# resistor-rc-filters.net
KiCad netlist of a schematic drawn in EAGLE
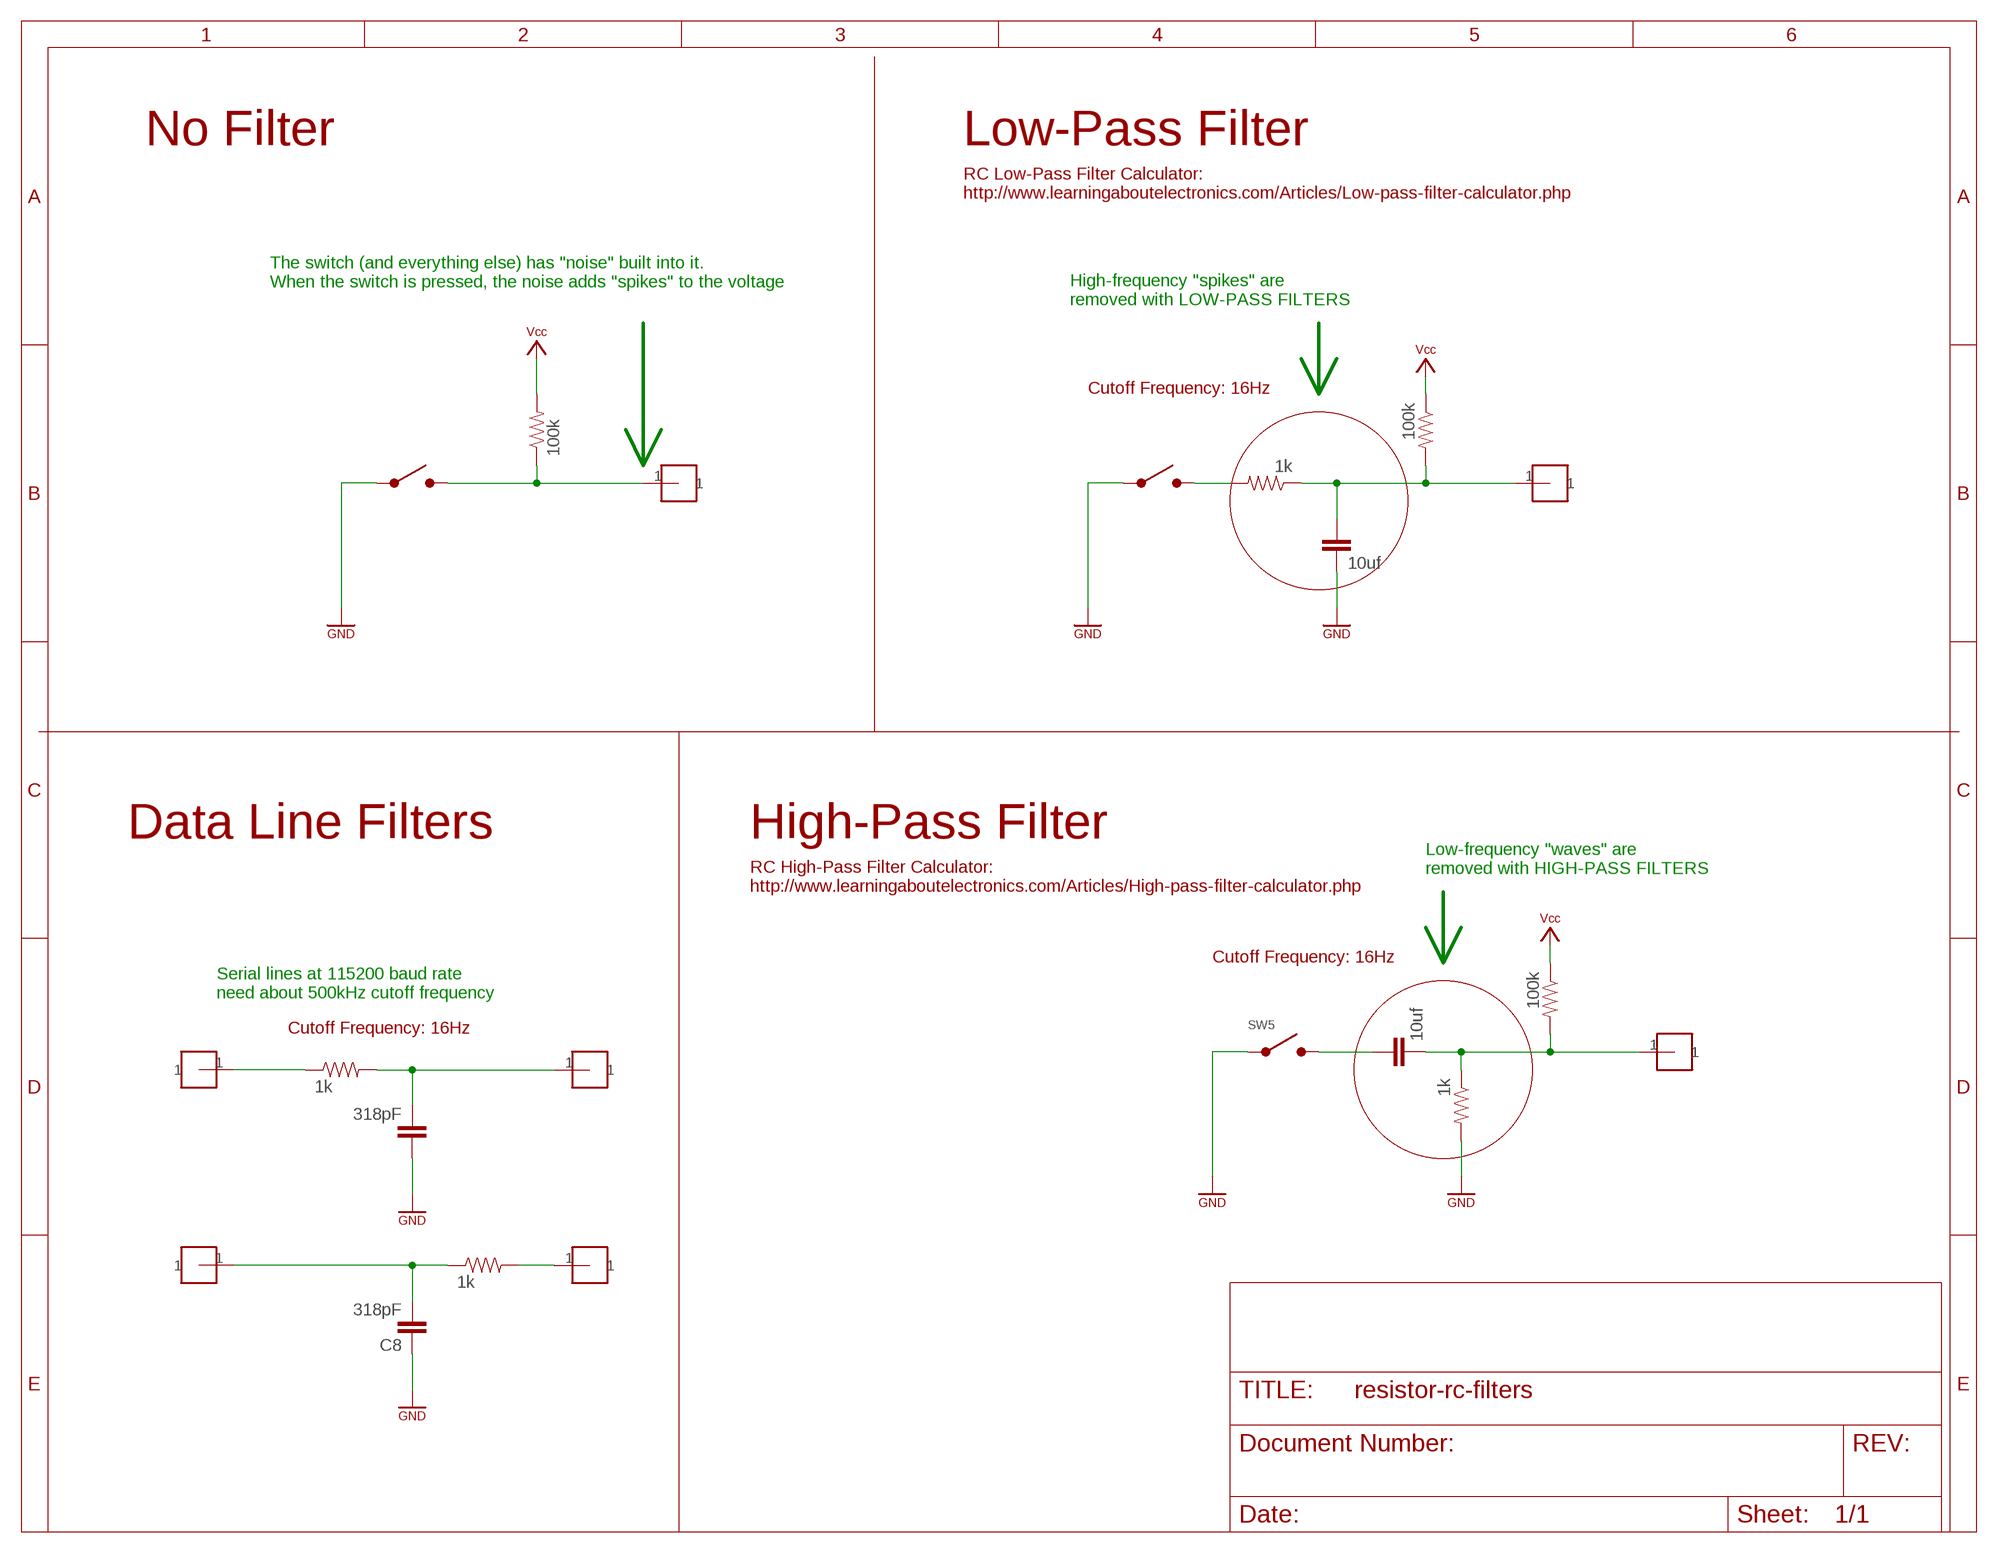
[diagram p0: schematic, sheet 1]

(export (version "E")
  (design (tool "Eeschema 10.0.6"))
  (components
    (comp (ref "C5")
      (value "10uf")
      (footprint "eagle-import:0805")
      (libsource (lib "eagle-import") (part "COMPONENT_CAP-0805"))
    )
    (comp (ref "C6")
      (value "10uf")
      (footprint "eagle-import:0805")
      (libsource (lib "eagle-import") (part "COMPONENT_CAP-0805"))
    )
    (comp (ref "C7")
      (value "318pF")
      (footprint "eagle-import:0805")
      (libsource (lib "eagle-import") (part "COMPONENT_CAP-0805"))
    )
    (comp (ref "C8")
      (value "318pF")
      (footprint "eagle-import:0805")
      (libsource (lib "eagle-import") (part "COMPONENT_CAP-0805"))
    )
    (comp (ref "R8")
      (value "100k")
      (footprint "eagle-import:0805")
      (libsource (lib "eagle-import") (part "COMPONENT_RESISTOR-0805"))
    )
    (comp (ref "R9")
      (value "1k")
      (footprint "eagle-import:0805")
      (libsource (lib "eagle-import") (part "COMPONENT_RESISTOR-0805"))
    )
    (comp (ref "R10")
      (value "100k")
      (footprint "eagle-import:0805")
      (libsource (lib "eagle-import") (part "COMPONENT_RESISTOR-0805"))
    )
    (comp (ref "R11")
      (value "100k")
      (footprint "eagle-import:0805")
      (libsource (lib "eagle-import") (part "COMPONENT_RESISTOR-0805"))
    )
    (comp (ref "R12")
      (value "1k")
      (footprint "eagle-import:0805")
      (libsource (lib "eagle-import") (part "COMPONENT_RESISTOR-0805"))
    )
    (comp (ref "R13")
      (value "1k")
      (footprint "eagle-import:0805")
      (libsource (lib "eagle-import") (part "COMPONENT_RESISTOR-0805"))
    )
    (comp (ref "R14")
      (value "1k")
      (footprint "eagle-import:0805")
      (libsource (lib "eagle-import") (part "COMPONENT_RESISTOR-0805"))
    )
    (comp (ref "SW4")
      (value "SWITCH_BUTTON_SPST")
      (footprint "eagle-import:7914G-1-000E")
      (libsource (lib "eagle-import") (part "SWITCH_BUTTON_SPST"))
    )
    (comp (ref "SW5")
      (value "SWITCH_BUTTON_SPST")
      (footprint "eagle-import:7914G-1-000E")
      (libsource (lib "eagle-import") (part "SWITCH_BUTTON_SPST"))
    )
    (comp (ref "SW6")
      (value "SWITCH_BUTTON_SPST")
      (footprint "eagle-import:7914G-1-000E")
      (libsource (lib "eagle-import") (part "SWITCH_BUTTON_SPST"))
    )
    (comp (ref "U$1")
      (value "HEADER-1-TESTPOINT")
      (footprint "eagle-import:TESTPOINT-1")
      (libsource (lib "eagle-import") (part "HEADER-1-TESTPOINT"))
    )
    (comp (ref "U$2")
      (value "HEADER-1-TESTPOINT")
      (footprint "eagle-import:TESTPOINT-1")
      (libsource (lib "eagle-import") (part "HEADER-1-TESTPOINT"))
    )
    (comp (ref "U$3")
      (value "HEADER-1-TESTPOINT")
      (footprint "eagle-import:TESTPOINT-1")
      (libsource (lib "eagle-import") (part "HEADER-1-TESTPOINT"))
    )
    (comp (ref "U$4")
      (value "HEADER-1-TESTPOINT")
      (footprint "eagle-import:TESTPOINT-1")
      (libsource (lib "eagle-import") (part "HEADER-1-TESTPOINT"))
    )
    (comp (ref "U$5")
      (value "HEADER-1-TESTPOINT")
      (footprint "eagle-import:TESTPOINT-1")
      (libsource (lib "eagle-import") (part "HEADER-1-TESTPOINT"))
    )
    (comp (ref "U$6")
      (value "HEADER-1-TESTPOINT")
      (footprint "eagle-import:TESTPOINT-1")
      (libsource (lib "eagle-import") (part "HEADER-1-TESTPOINT"))
    )
    (comp (ref "U$7")
      (value "HEADER-1-TESTPOINT")
      (footprint "eagle-import:TESTPOINT-1")
      (libsource (lib "eagle-import") (part "HEADER-1-TESTPOINT"))
    )
  )
  (nets
    (net (code "1") (name "Net-(C5-Pad1)") (class "Default")
      (node (ref "C5") (pin "1") (pinfunction "1_1") (pintype "passive"))
      (node (ref "R10") (pin "2") (pinfunction "2_2") (pintype "passive"))
      (node (ref "R9") (pin "1") (pinfunction "1_1") (pintype "passive"))
      (node (ref "U$6") (pin "1") (pinfunction "1_1") (pintype "bidirectional"))
    )
    (net (code "2") (name "Net-(C6-Pad1)") (class "Default")
      (node (ref "C6") (pin "1") (pinfunction "1_1") (pintype "passive"))
      (node (ref "SW5") (pin "2A") (pinfunction "2_2A") (pintype "bidirectional"))
      (node (ref "SW5") (pin "2B") (pinfunction "2_2B") (pintype "bidirectional"))
    )
    (net (code "3") (name "Net-(C6-Pad2)") (class "Default")
      (node (ref "C6") (pin "2") (pinfunction "2_2") (pintype "passive"))
      (node (ref "R11") (pin "2") (pinfunction "2_2") (pintype "passive"))
      (node (ref "R12") (pin "1") (pinfunction "1_1") (pintype "passive"))
      (node (ref "U$7") (pin "1") (pinfunction "1_1") (pintype "bidirectional"))
    )
    (net (code "4") (name "Net-(C7-Pad2)") (class "Default")
      (node (ref "C7") (pin "2") (pinfunction "2_2") (pintype "passive"))
      (node (ref "R14") (pin "2") (pinfunction "2_2") (pintype "passive"))
      (node (ref "U$2") (pin "1") (pinfunction "1_1") (pintype "bidirectional"))
    )
    (net (code "5") (name "Net-(C8-Pad2)") (class "Default")
      (node (ref "C8") (pin "2") (pinfunction "2_2") (pintype "passive"))
      (node (ref "R13") (pin "1") (pinfunction "1_1") (pintype "passive"))
      (node (ref "U$4") (pin "1") (pinfunction "1_1") (pintype "bidirectional"))
    )
    (net (code "6") (name "Net-(R8-Pad1)") (class "Default")
      (node (ref "R8") (pin "1") (pinfunction "1_1") (pintype "passive"))
      (node (ref "SW4") (pin "2A") (pinfunction "2_2A") (pintype "bidirectional"))
      (node (ref "SW4") (pin "2B") (pinfunction "2_2B") (pintype "bidirectional"))
      (node (ref "U$5") (pin "1") (pinfunction "1_1") (pintype "bidirectional"))
    )
    (net (code "7") (name "Net-(R9-Pad2)") (class "Default")
      (node (ref "R9") (pin "2") (pinfunction "2_2") (pintype "passive"))
      (node (ref "SW6") (pin "2A") (pinfunction "2_2A") (pintype "bidirectional"))
      (node (ref "SW6") (pin "2B") (pinfunction "2_2B") (pintype "bidirectional"))
    )
    (net (code "8") (name "Net-(R13-Pad2)") (class "Default")
      (node (ref "R13") (pin "2") (pinfunction "2_2") (pintype "passive"))
      (node (ref "U$1") (pin "1") (pinfunction "1_1") (pintype "bidirectional"))
    )
    (net (code "9") (name "Net-(R14-Pad1)") (class "Default")
      (node (ref "R14") (pin "1") (pinfunction "1_1") (pintype "passive"))
      (node (ref "U$3") (pin "1") (pinfunction "1_1") (pintype "bidirectional"))
    )
    (net (code "10") (name "SYMBOL_GND") (class "Default")
      (node (ref "C5") (pin "2") (pinfunction "2_2") (pintype "passive"))
      (node (ref "C7") (pin "1") (pinfunction "1_1") (pintype "passive"))
      (node (ref "C8") (pin "1") (pinfunction "1_1") (pintype "passive"))
      (node (ref "R12") (pin "2") (pinfunction "2_2") (pintype "passive"))
      (node (ref "SW4") (pin "1A") (pinfunction "1_1A") (pintype "bidirectional"))
      (node (ref "SW4") (pin "1B") (pinfunction "1_1B") (pintype "bidirectional"))
      (node (ref "SW5") (pin "1A") (pinfunction "1_1A") (pintype "bidirectional"))
      (node (ref "SW5") (pin "1B") (pinfunction "1_1B") (pintype "bidirectional"))
      (node (ref "SW6") (pin "1A") (pinfunction "1_1A") (pintype "bidirectional"))
      (node (ref "SW6") (pin "1B") (pinfunction "1_1B") (pintype "bidirectional"))
    )
    (net (code "11") (name "SYMBOL_VCC") (class "Default")
      (node (ref "R10") (pin "1") (pinfunction "1_1") (pintype "passive"))
      (node (ref "R11") (pin "1") (pinfunction "1_1") (pintype "passive"))
      (node (ref "R8") (pin "2") (pinfunction "2_2") (pintype "passive"))
    )
  )
)
